# DGL.net
KiCad netlist of a schematic drawn in EAGLE
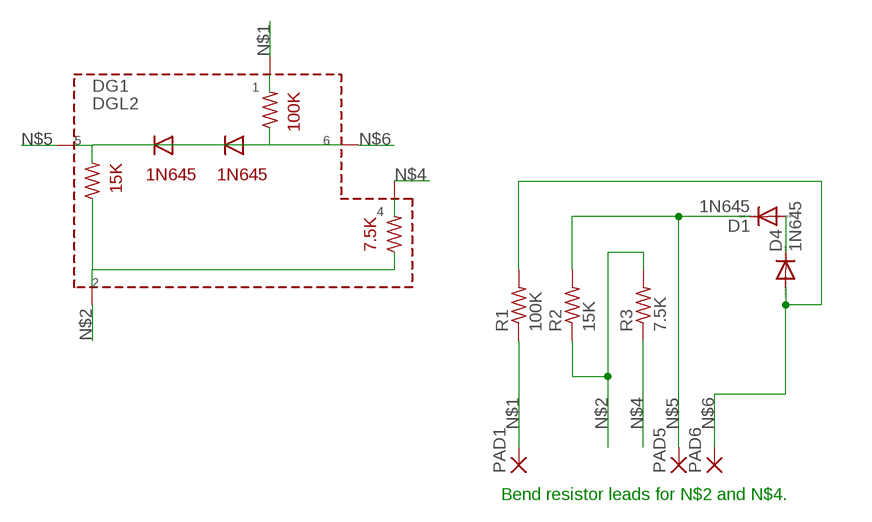
[diagram p0: schematic, sheet 1]

(export (version "E")
  (design (tool "Eeschema 10.0.6"))
  (components
    (comp (ref "D1")
      (value "1N645")
      (footprint "eagle-import:DO34-7")
      (libsource (lib "eagle-import") (part "DIODE-DO34-7"))
    )
    (comp (ref "D4")
      (value "1N645")
      (footprint "eagle-import:DO34-7")
      (libsource (lib "eagle-import") (part "DIODE-DO34-7"))
    )
    (comp (ref "DG1")
      (value "DGL2")
      (footprint "eagle-import:DGL2")
      (libsource (lib "eagle-import") (part "DGL2"))
    )
    (comp (ref "PAD1")
      (value "1,6/0,8")
      (footprint "eagle-import:1,6_0,8")
      (libsource (lib "eagle-import") (part "1,6/0,8"))
    )
    (comp (ref "PAD5")
      (value "1,6/0,8")
      (footprint "eagle-import:1,6_0,8")
      (libsource (lib "eagle-import") (part "1,6/0,8"))
    )
    (comp (ref "PAD6")
      (value "1,6/0,8")
      (footprint "eagle-import:1,6_0,8")
      (libsource (lib "eagle-import") (part "1,6/0,8"))
    )
    (comp (ref "R1")
      (value "100K")
      (footprint "eagle-import:0207_7")
      (libsource (lib "eagle-import") (part "R-US_0207/7"))
    )
    (comp (ref "R2")
      (value "15K")
      (footprint "eagle-import:0207_7")
      (libsource (lib "eagle-import") (part "R-US_0207/7"))
    )
    (comp (ref "R3")
      (value "7.5K")
      (footprint "eagle-import:0207_7")
      (libsource (lib "eagle-import") (part "R-US_0207/7"))
    )
  )
  (nets
    (net (code "1") (name "/N$1") (class "Default")
      (node (ref "DG1") (pin "P$1") (pinfunction "1_P$1") (pintype "passive"))
      (node (ref "PAD1") (pin "1") (pinfunction "P_1") (pintype "passive"))
      (node (ref "R1") (pin "1") (pinfunction "1_1") (pintype "passive"))
    )
    (net (code "2") (name "/N$2") (class "Default")
      (node (ref "DG1") (pin "P$2") (pinfunction "2_P$2") (pintype "passive"))
      (node (ref "R2") (pin "1") (pinfunction "1_1") (pintype "passive"))
      (node (ref "R3") (pin "2") (pinfunction "2_2") (pintype "passive"))
    )
    (net (code "3") (name "/N$4") (class "Default")
      (node (ref "DG1") (pin "P$4") (pinfunction "4_P$4") (pintype "passive"))
      (node (ref "R3") (pin "1") (pinfunction "1_1") (pintype "passive"))
    )
    (net (code "4") (name "/N$5") (class "Default")
      (node (ref "D1") (pin "C") (pinfunction "C_C") (pintype "passive"))
      (node (ref "DG1") (pin "P$5") (pinfunction "5_P$5") (pintype "passive"))
      (node (ref "PAD5") (pin "1") (pinfunction "P_1") (pintype "passive"))
      (node (ref "R2") (pin "2") (pinfunction "2_2") (pintype "passive"))
    )
    (net (code "5") (name "/N$6") (class "Default")
      (node (ref "D4") (pin "A") (pinfunction "A_A") (pintype "passive"))
      (node (ref "DG1") (pin "P$6") (pinfunction "6_P$6") (pintype "passive"))
      (node (ref "PAD6") (pin "1") (pinfunction "P_1") (pintype "passive"))
      (node (ref "R1") (pin "2") (pinfunction "2_2") (pintype "passive"))
    )
    (net (code "6") (name "Net-(D1-PadA)") (class "Default")
      (node (ref "D1") (pin "A") (pinfunction "A_A") (pintype "passive"))
      (node (ref "D4") (pin "C") (pinfunction "C_C") (pintype "passive"))
    )
  )
)
